# R113X.net
KiCad netlist of a schematic drawn in EAGLE
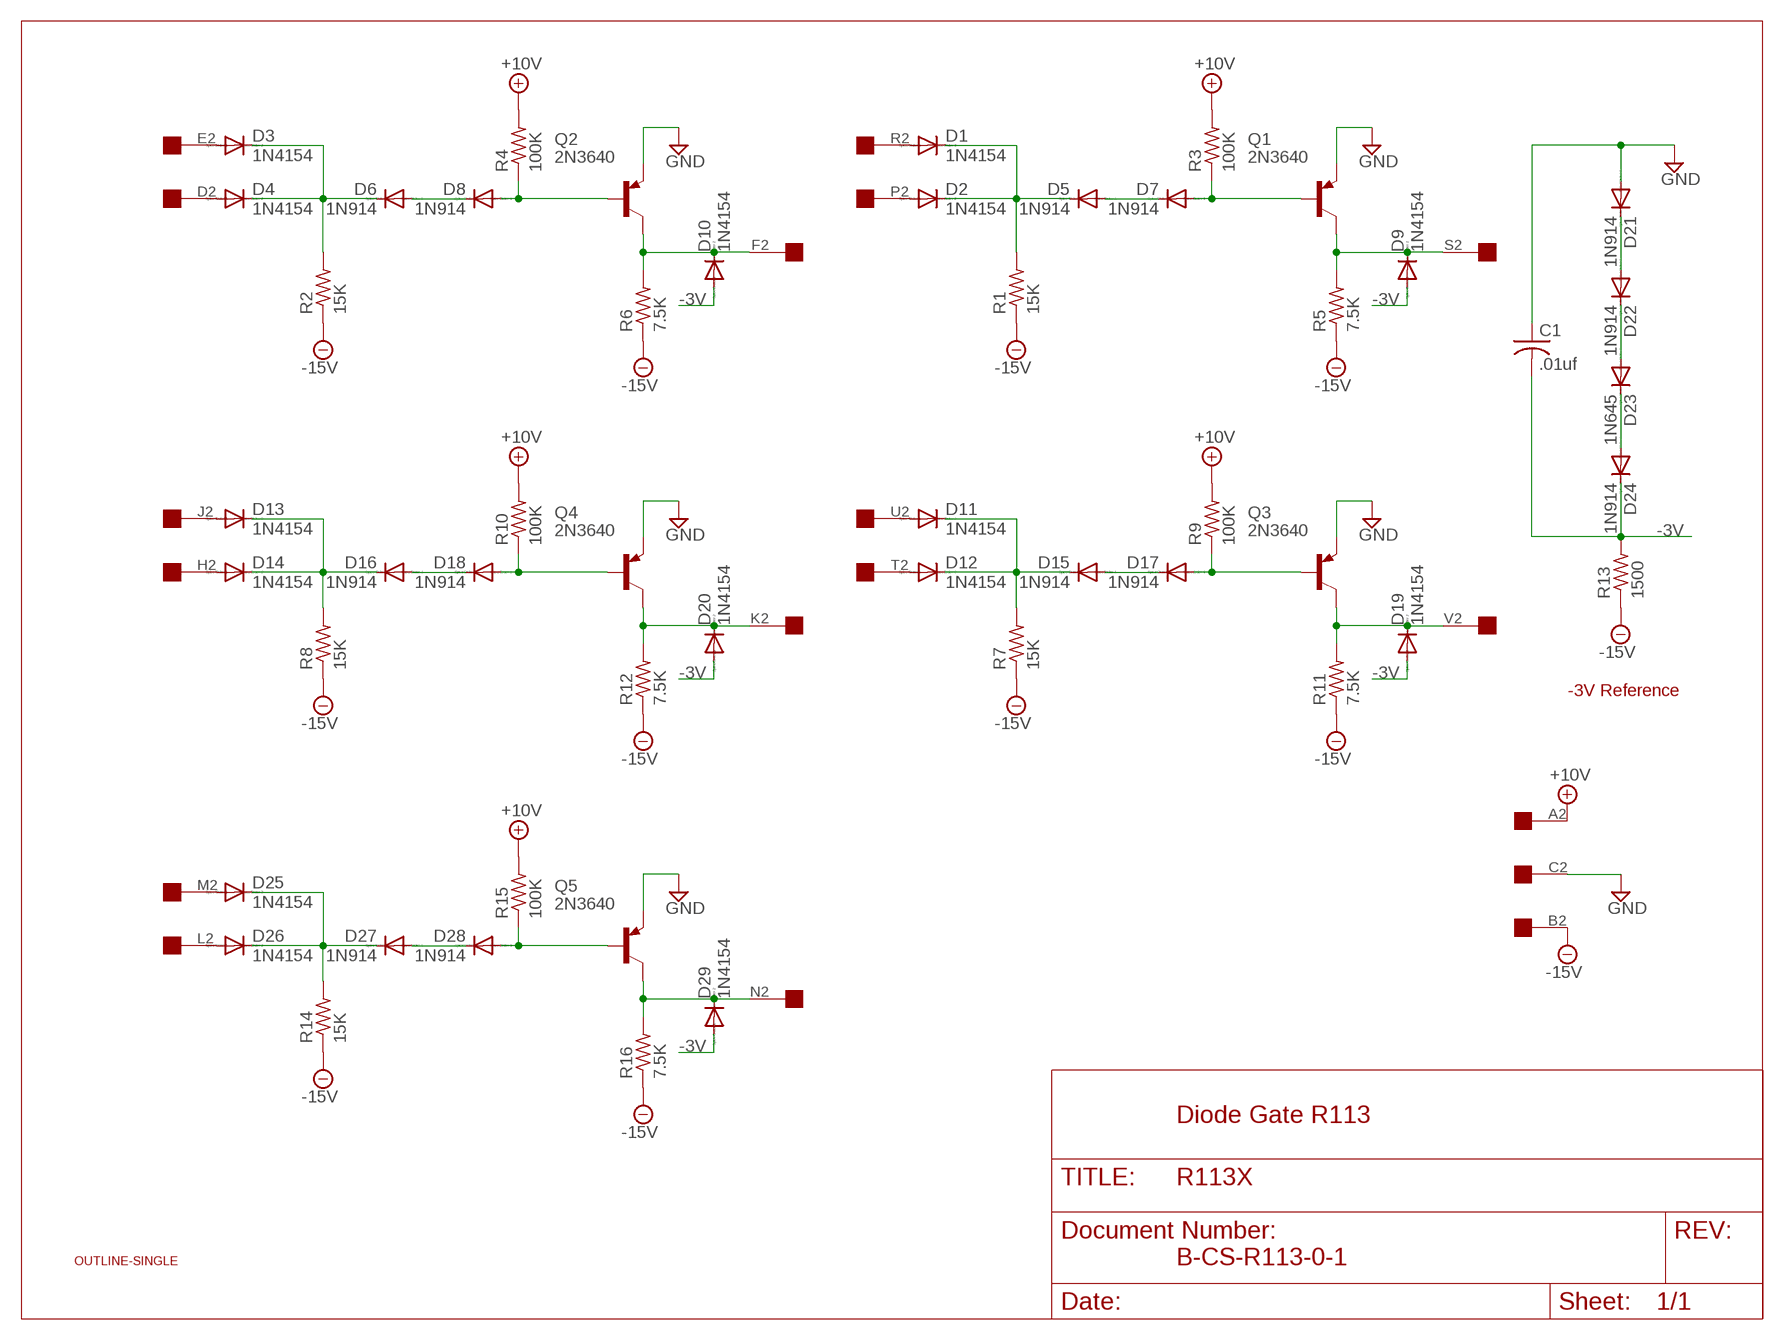
[diagram p0: schematic, sheet 1]

(export (version "E")
  (design (tool "Eeschema 10.0.6"))
  (components
    (comp (ref "C1")
      (value ".01uf")
      (footprint "eagle-import:C050-025X075")
      (libsource (lib "eagle-import") (part "C-US050-025X075"))
    )
    (comp (ref "D1")
      (value "1N4154")
      (footprint "eagle-import:DO35-10")
      (libsource (lib "eagle-import") (part "1N4148DO35-10"))
    )
    (comp (ref "D2")
      (value "1N4154")
      (footprint "eagle-import:DO35-10")
      (libsource (lib "eagle-import") (part "1N4148DO35-10"))
    )
    (comp (ref "D3")
      (value "1N4154")
      (footprint "eagle-import:DO35-10")
      (libsource (lib "eagle-import") (part "1N4148DO35-10"))
    )
    (comp (ref "D4")
      (value "1N4154")
      (footprint "eagle-import:DO35-10")
      (libsource (lib "eagle-import") (part "1N4148DO35-10"))
    )
    (comp (ref "D5")
      (value "1N914")
      (footprint "eagle-import:DO35-10")
      (libsource (lib "eagle-import") (part "1N4148DO35-10"))
    )
    (comp (ref "D6")
      (value "1N914")
      (footprint "eagle-import:DO35-10")
      (libsource (lib "eagle-import") (part "1N4148DO35-10"))
    )
    (comp (ref "D7")
      (value "1N914")
      (footprint "eagle-import:DO35-10")
      (libsource (lib "eagle-import") (part "1N4148DO35-10"))
    )
    (comp (ref "D8")
      (value "1N914")
      (footprint "eagle-import:DO35-10")
      (libsource (lib "eagle-import") (part "1N4148DO35-10"))
    )
    (comp (ref "D9")
      (value "1N4154")
      (footprint "eagle-import:DO35-10")
      (libsource (lib "eagle-import") (part "1N4148DO35-10"))
    )
    (comp (ref "D10")
      (value "1N4154")
      (footprint "eagle-import:DO35-10")
      (libsource (lib "eagle-import") (part "1N4148DO35-10"))
    )
    (comp (ref "D11")
      (value "1N4154")
      (footprint "eagle-import:DO35-10")
      (libsource (lib "eagle-import") (part "1N4148DO35-10"))
    )
    (comp (ref "D12")
      (value "1N4154")
      (footprint "eagle-import:DO35-10")
      (libsource (lib "eagle-import") (part "1N4148DO35-10"))
    )
    (comp (ref "D13")
      (value "1N4154")
      (footprint "eagle-import:DO35-10")
      (libsource (lib "eagle-import") (part "1N4148DO35-10"))
    )
    (comp (ref "D14")
      (value "1N4154")
      (footprint "eagle-import:DO35-10")
      (libsource (lib "eagle-import") (part "1N4148DO35-10"))
    )
    (comp (ref "D15")
      (value "1N914")
      (footprint "eagle-import:DO35-10")
      (libsource (lib "eagle-import") (part "1N4148DO35-10"))
    )
    (comp (ref "D16")
      (value "1N914")
      (footprint "eagle-import:DO35-10")
      (libsource (lib "eagle-import") (part "1N4148DO35-10"))
    )
    (comp (ref "D17")
      (value "1N914")
      (footprint "eagle-import:DO35-10")
      (libsource (lib "eagle-import") (part "1N4148DO35-10"))
    )
    (comp (ref "D18")
      (value "1N914")
      (footprint "eagle-import:DO35-10")
      (libsource (lib "eagle-import") (part "1N4148DO35-10"))
    )
    (comp (ref "D19")
      (value "1N4154")
      (footprint "eagle-import:DO35-10")
      (libsource (lib "eagle-import") (part "1N4148DO35-10"))
    )
    (comp (ref "D20")
      (value "1N4154")
      (footprint "eagle-import:DO35-10")
      (libsource (lib "eagle-import") (part "1N4148DO35-10"))
    )
    (comp (ref "D21")
      (value "1N914")
      (footprint "eagle-import:DO35-10")
      (libsource (lib "eagle-import") (part "1N4148DO35-10"))
    )
    (comp (ref "D22")
      (value "1N914")
      (footprint "eagle-import:DO35-10")
      (libsource (lib "eagle-import") (part "1N4148DO35-10"))
    )
    (comp (ref "D23")
      (value "1N645")
      (footprint "eagle-import:DO35-10")
      (libsource (lib "eagle-import") (part "1N4148DO35-10"))
    )
    (comp (ref "D24")
      (value "1N914")
      (footprint "eagle-import:DO35-10")
      (libsource (lib "eagle-import") (part "1N4148DO35-10"))
    )
    (comp (ref "D25")
      (value "1N4154")
      (footprint "eagle-import:DO35-10")
      (libsource (lib "eagle-import") (part "1N4148DO35-10"))
    )
    (comp (ref "D26")
      (value "1N4154")
      (footprint "eagle-import:DO35-10")
      (libsource (lib "eagle-import") (part "1N4148DO35-10"))
    )
    (comp (ref "D27")
      (value "1N914")
      (footprint "eagle-import:DO35-10")
      (libsource (lib "eagle-import") (part "1N4148DO35-10"))
    )
    (comp (ref "D28")
      (value "1N914")
      (footprint "eagle-import:DO35-10")
      (libsource (lib "eagle-import") (part "1N4148DO35-10"))
    )
    (comp (ref "D29")
      (value "1N4154")
      (footprint "eagle-import:DO35-10")
      (libsource (lib "eagle-import") (part "1N4148DO35-10"))
    )
    (comp (ref "Q1")
      (value "2N3640")
      (footprint "eagle-import:TO39")
      (libsource (lib "eagle-import") (part "2N3637"))
    )
    (comp (ref "Q2")
      (value "2N3640")
      (footprint "eagle-import:TO39")
      (libsource (lib "eagle-import") (part "2N3637"))
    )
    (comp (ref "Q3")
      (value "2N3640")
      (footprint "eagle-import:TO39")
      (libsource (lib "eagle-import") (part "2N3637"))
    )
    (comp (ref "Q4")
      (value "2N3640")
      (footprint "eagle-import:TO39")
      (libsource (lib "eagle-import") (part "2N3637"))
    )
    (comp (ref "Q5")
      (value "2N3640")
      (footprint "eagle-import:TO39")
      (libsource (lib "eagle-import") (part "2N3637"))
    )
    (comp (ref "R1")
      (value "15K")
      (footprint "eagle-import:0207_10")
      (libsource (lib "eagle-import") (part "R-US_0207/10"))
    )
    (comp (ref "R2")
      (value "15K")
      (footprint "eagle-import:0207_10")
      (libsource (lib "eagle-import") (part "R-US_0207/10"))
    )
    (comp (ref "R3")
      (value "100K")
      (footprint "eagle-import:0207_10")
      (libsource (lib "eagle-import") (part "R-US_0207/10"))
    )
    (comp (ref "R4")
      (value "100K")
      (footprint "eagle-import:0207_10")
      (libsource (lib "eagle-import") (part "R-US_0207/10"))
    )
    (comp (ref "R5")
      (value "7.5K")
      (footprint "eagle-import:0207_10")
      (libsource (lib "eagle-import") (part "R-US_0207/10"))
    )
    (comp (ref "R6")
      (value "7.5K")
      (footprint "eagle-import:0207_10")
      (libsource (lib "eagle-import") (part "R-US_0207/10"))
    )
    (comp (ref "R7")
      (value "15K")
      (footprint "eagle-import:0207_10")
      (libsource (lib "eagle-import") (part "R-US_0207/10"))
    )
    (comp (ref "R8")
      (value "15K")
      (footprint "eagle-import:0207_10")
      (libsource (lib "eagle-import") (part "R-US_0207/10"))
    )
    (comp (ref "R9")
      (value "100K")
      (footprint "eagle-import:0207_10")
      (libsource (lib "eagle-import") (part "R-US_0207/10"))
    )
    (comp (ref "R10")
      (value "100K")
      (footprint "eagle-import:0207_10")
      (libsource (lib "eagle-import") (part "R-US_0207/10"))
    )
    (comp (ref "R11")
      (value "7.5K")
      (footprint "eagle-import:0207_10")
      (libsource (lib "eagle-import") (part "R-US_0207/10"))
    )
    (comp (ref "R12")
      (value "7.5K")
      (footprint "eagle-import:0207_10")
      (libsource (lib "eagle-import") (part "R-US_0207/10"))
    )
    (comp (ref "R13")
      (value "1500")
      (footprint "eagle-import:0207_10")
      (libsource (lib "eagle-import") (part "R-US_0207/10"))
    )
    (comp (ref "R14")
      (value "15K")
      (footprint "eagle-import:0207_10")
      (libsource (lib "eagle-import") (part "R-US_0207/10"))
    )
    (comp (ref "R15")
      (value "100K")
      (footprint "eagle-import:0207_10")
      (libsource (lib "eagle-import") (part "R-US_0207/10"))
    )
    (comp (ref "R16")
      (value "7.5K")
      (footprint "eagle-import:0207_10")
      (libsource (lib "eagle-import") (part "R-US_0207/10"))
    )
    (comp (ref "U$1")
      (value "OUTLINE-SINGLE")
      (footprint "eagle-import:SINGLE")
      (libsource (lib "eagle-import") (part "OUTLINE-SINGLE"))
    )
    (comp (ref "U$2")
      (value "EDGE-1")
      (footprint "eagle-import:EDGE-CON1")
      (libsource (lib "eagle-import") (part "EDGE-1"))
    )
  )
  (nets
    (net (code "1") (name "+10V") (class "Default")
      (node (ref "R10") (pin "2") (pinfunction "2_2") (pintype "passive"))
      (node (ref "R15") (pin "2") (pinfunction "2_2") (pintype "passive"))
      (node (ref "R3") (pin "2") (pinfunction "2_2") (pintype "passive"))
      (node (ref "R4") (pin "2") (pinfunction "2_2") (pintype "passive"))
      (node (ref "R9") (pin "2") (pinfunction "2_2") (pintype "passive"))
      (node (ref "U$2") (pin "A2") (pinfunction "1_A2") (pintype "bidirectional"))
    )
    (net (code "2") (name "-15V") (class "Default")
      (node (ref "R1") (pin "1") (pinfunction "1_1") (pintype "passive"))
      (node (ref "R11") (pin "1") (pinfunction "1_1") (pintype "passive"))
      (node (ref "R12") (pin "1") (pinfunction "1_1") (pintype "passive"))
      (node (ref "R13") (pin "1") (pinfunction "1_1") (pintype "passive"))
      (node (ref "R14") (pin "1") (pinfunction "1_1") (pintype "passive"))
      (node (ref "R16") (pin "1") (pinfunction "1_1") (pintype "passive"))
      (node (ref "R2") (pin "1") (pinfunction "1_1") (pintype "passive"))
      (node (ref "R5") (pin "1") (pinfunction "1_1") (pintype "passive"))
      (node (ref "R6") (pin "1") (pinfunction "1_1") (pintype "passive"))
      (node (ref "R7") (pin "1") (pinfunction "1_1") (pintype "passive"))
      (node (ref "R8") (pin "1") (pinfunction "1_1") (pintype "passive"))
      (node (ref "U$2") (pin "B2") (pinfunction "1_B2") (pintype "bidirectional"))
    )
    (net (code "3") (name "/-3V") (class "Default")
      (node (ref "C1") (pin "2") (pinfunction "2_2") (pintype "passive"))
      (node (ref "D10") (pin "A") (pinfunction "A_A") (pintype "passive"))
      (node (ref "D19") (pin "A") (pinfunction "A_A") (pintype "passive"))
      (node (ref "D20") (pin "A") (pinfunction "A_A") (pintype "passive"))
      (node (ref "D24") (pin "C") (pinfunction "C_C") (pintype "passive"))
      (node (ref "D29") (pin "A") (pinfunction "A_A") (pintype "passive"))
      (node (ref "D9") (pin "A") (pinfunction "A_A") (pintype "passive"))
      (node (ref "R13") (pin "2") (pinfunction "2_2") (pintype "passive"))
    )
    (net (code "4") (name "GND") (class "Default")
      (node (ref "C1") (pin "1") (pinfunction "1_1") (pintype "passive"))
      (node (ref "D21") (pin "A") (pinfunction "A_A") (pintype "passive"))
      (node (ref "Q1") (pin "1") (pinfunction "E_1") (pintype "passive"))
      (node (ref "Q2") (pin "1") (pinfunction "E_1") (pintype "passive"))
      (node (ref "Q3") (pin "1") (pinfunction "E_1") (pintype "passive"))
      (node (ref "Q4") (pin "1") (pinfunction "E_1") (pintype "passive"))
      (node (ref "Q5") (pin "1") (pinfunction "E_1") (pintype "passive"))
      (node (ref "U$2") (pin "C2") (pinfunction "1_C2") (pintype "bidirectional"))
    )
    (net (code "5") (name "Net-(D1-PadC)") (class "Default")
      (node (ref "D1") (pin "C") (pinfunction "C_C") (pintype "passive"))
      (node (ref "D2") (pin "C") (pinfunction "C_C") (pintype "passive"))
      (node (ref "D5") (pin "C") (pinfunction "C_C") (pintype "passive"))
      (node (ref "R1") (pin "2") (pinfunction "2_2") (pintype "passive"))
    )
    (net (code "6") (name "Net-(D3-PadC)") (class "Default")
      (node (ref "D3") (pin "C") (pinfunction "C_C") (pintype "passive"))
      (node (ref "D4") (pin "C") (pinfunction "C_C") (pintype "passive"))
      (node (ref "D6") (pin "C") (pinfunction "C_C") (pintype "passive"))
      (node (ref "R2") (pin "2") (pinfunction "2_2") (pintype "passive"))
    )
    (net (code "7") (name "Net-(D5-PadA)") (class "Default")
      (node (ref "D5") (pin "A") (pinfunction "A_A") (pintype "passive"))
      (node (ref "D7") (pin "C") (pinfunction "C_C") (pintype "passive"))
    )
    (net (code "8") (name "Net-(D6-PadA)") (class "Default")
      (node (ref "D6") (pin "A") (pinfunction "A_A") (pintype "passive"))
      (node (ref "D8") (pin "C") (pinfunction "C_C") (pintype "passive"))
    )
    (net (code "9") (name "Net-(D11-PadC)") (class "Default")
      (node (ref "D11") (pin "C") (pinfunction "C_C") (pintype "passive"))
      (node (ref "D12") (pin "C") (pinfunction "C_C") (pintype "passive"))
      (node (ref "D15") (pin "C") (pinfunction "C_C") (pintype "passive"))
      (node (ref "R7") (pin "2") (pinfunction "2_2") (pintype "passive"))
    )
    (net (code "10") (name "Net-(D13-PadC)") (class "Default")
      (node (ref "D13") (pin "C") (pinfunction "C_C") (pintype "passive"))
      (node (ref "D14") (pin "C") (pinfunction "C_C") (pintype "passive"))
      (node (ref "D16") (pin "C") (pinfunction "C_C") (pintype "passive"))
      (node (ref "R8") (pin "2") (pinfunction "2_2") (pintype "passive"))
    )
    (net (code "11") (name "Net-(D15-PadA)") (class "Default")
      (node (ref "D15") (pin "A") (pinfunction "A_A") (pintype "passive"))
      (node (ref "D17") (pin "C") (pinfunction "C_C") (pintype "passive"))
    )
    (net (code "12") (name "Net-(D16-PadA)") (class "Default")
      (node (ref "D16") (pin "A") (pinfunction "A_A") (pintype "passive"))
      (node (ref "D18") (pin "C") (pinfunction "C_C") (pintype "passive"))
    )
    (net (code "13") (name "Net-(D21-PadC)") (class "Default")
      (node (ref "D21") (pin "C") (pinfunction "C_C") (pintype "passive"))
      (node (ref "D22") (pin "A") (pinfunction "A_A") (pintype "passive"))
    )
    (net (code "14") (name "Net-(D22-PadC)") (class "Default")
      (node (ref "D22") (pin "C") (pinfunction "C_C") (pintype "passive"))
      (node (ref "D23") (pin "A") (pinfunction "A_A") (pintype "passive"))
    )
    (net (code "15") (name "Net-(D23-PadC)") (class "Default")
      (node (ref "D23") (pin "C") (pinfunction "C_C") (pintype "passive"))
      (node (ref "D24") (pin "A") (pinfunction "A_A") (pintype "passive"))
    )
    (net (code "16") (name "Net-(D25-PadC)") (class "Default")
      (node (ref "D25") (pin "C") (pinfunction "C_C") (pintype "passive"))
      (node (ref "D26") (pin "C") (pinfunction "C_C") (pintype "passive"))
      (node (ref "D27") (pin "C") (pinfunction "C_C") (pintype "passive"))
      (node (ref "R14") (pin "2") (pinfunction "2_2") (pintype "passive"))
    )
    (net (code "17") (name "Net-(D27-PadA)") (class "Default")
      (node (ref "D27") (pin "A") (pinfunction "A_A") (pintype "passive"))
      (node (ref "D28") (pin "C") (pinfunction "C_C") (pintype "passive"))
    )
    (net (code "18") (name "Net-(Q1-B)") (class "Default")
      (node (ref "D7") (pin "A") (pinfunction "A_A") (pintype "passive"))
      (node (ref "Q1") (pin "2") (pinfunction "B_2") (pintype "passive"))
      (node (ref "R3") (pin "1") (pinfunction "1_1") (pintype "passive"))
    )
    (net (code "19") (name "Net-(Q1-C)") (class "Default")
      (node (ref "D9") (pin "C") (pinfunction "C_C") (pintype "passive"))
      (node (ref "Q1") (pin "3") (pinfunction "C_3") (pintype "passive"))
      (node (ref "R5") (pin "2") (pinfunction "2_2") (pintype "passive"))
      (node (ref "U$2") (pin "S2") (pinfunction "1_S2") (pintype "bidirectional"))
    )
    (net (code "20") (name "Net-(Q2-B)") (class "Default")
      (node (ref "D8") (pin "A") (pinfunction "A_A") (pintype "passive"))
      (node (ref "Q2") (pin "2") (pinfunction "B_2") (pintype "passive"))
      (node (ref "R4") (pin "1") (pinfunction "1_1") (pintype "passive"))
    )
    (net (code "21") (name "Net-(Q2-C)") (class "Default")
      (node (ref "D10") (pin "C") (pinfunction "C_C") (pintype "passive"))
      (node (ref "Q2") (pin "3") (pinfunction "C_3") (pintype "passive"))
      (node (ref "R6") (pin "2") (pinfunction "2_2") (pintype "passive"))
      (node (ref "U$2") (pin "F2") (pinfunction "1_F2") (pintype "bidirectional"))
    )
    (net (code "22") (name "Net-(Q3-B)") (class "Default")
      (node (ref "D17") (pin "A") (pinfunction "A_A") (pintype "passive"))
      (node (ref "Q3") (pin "2") (pinfunction "B_2") (pintype "passive"))
      (node (ref "R9") (pin "1") (pinfunction "1_1") (pintype "passive"))
    )
    (net (code "23") (name "Net-(Q3-C)") (class "Default")
      (node (ref "D19") (pin "C") (pinfunction "C_C") (pintype "passive"))
      (node (ref "Q3") (pin "3") (pinfunction "C_3") (pintype "passive"))
      (node (ref "R11") (pin "2") (pinfunction "2_2") (pintype "passive"))
      (node (ref "U$2") (pin "V2") (pinfunction "1_V2") (pintype "bidirectional"))
    )
    (net (code "24") (name "Net-(Q4-B)") (class "Default")
      (node (ref "D18") (pin "A") (pinfunction "A_A") (pintype "passive"))
      (node (ref "Q4") (pin "2") (pinfunction "B_2") (pintype "passive"))
      (node (ref "R10") (pin "1") (pinfunction "1_1") (pintype "passive"))
    )
    (net (code "25") (name "Net-(Q4-C)") (class "Default")
      (node (ref "D20") (pin "C") (pinfunction "C_C") (pintype "passive"))
      (node (ref "Q4") (pin "3") (pinfunction "C_3") (pintype "passive"))
      (node (ref "R12") (pin "2") (pinfunction "2_2") (pintype "passive"))
      (node (ref "U$2") (pin "K2") (pinfunction "1_K2") (pintype "bidirectional"))
    )
    (net (code "26") (name "Net-(Q5-B)") (class "Default")
      (node (ref "D28") (pin "A") (pinfunction "A_A") (pintype "passive"))
      (node (ref "Q5") (pin "2") (pinfunction "B_2") (pintype "passive"))
      (node (ref "R15") (pin "1") (pinfunction "1_1") (pintype "passive"))
    )
    (net (code "27") (name "Net-(Q5-C)") (class "Default")
      (node (ref "D29") (pin "C") (pinfunction "C_C") (pintype "passive"))
      (node (ref "Q5") (pin "3") (pinfunction "C_3") (pintype "passive"))
      (node (ref "R16") (pin "2") (pinfunction "2_2") (pintype "passive"))
      (node (ref "U$2") (pin "N2") (pinfunction "1_N2") (pintype "bidirectional"))
    )
    (net (code "28") (name "Net-(U$2D-1)") (class "Default")
      (node (ref "D4") (pin "A") (pinfunction "A_A") (pintype "passive"))
      (node (ref "U$2") (pin "D2") (pinfunction "1_D2") (pintype "bidirectional"))
    )
    (net (code "29") (name "Net-(U$2E-1)") (class "Default")
      (node (ref "D3") (pin "A") (pinfunction "A_A") (pintype "passive"))
      (node (ref "U$2") (pin "E2") (pinfunction "1_E2") (pintype "bidirectional"))
    )
    (net (code "30") (name "Net-(U$2G-1)") (class "Default")
      (node (ref "D14") (pin "A") (pinfunction "A_A") (pintype "passive"))
      (node (ref "U$2") (pin "H2") (pinfunction "1_H2") (pintype "bidirectional"))
    )
    (net (code "31") (name "Net-(U$2H-1)") (class "Default")
      (node (ref "D13") (pin "A") (pinfunction "A_A") (pintype "passive"))
      (node (ref "U$2") (pin "J2") (pinfunction "1_J2") (pintype "bidirectional"))
    )
    (net (code "32") (name "Net-(U$2J-1)") (class "Default")
      (node (ref "D26") (pin "A") (pinfunction "A_A") (pintype "passive"))
      (node (ref "U$2") (pin "L2") (pinfunction "1_L2") (pintype "bidirectional"))
    )
    (net (code "33") (name "Net-(U$2K-1)") (class "Default")
      (node (ref "D25") (pin "A") (pinfunction "A_A") (pintype "passive"))
      (node (ref "U$2") (pin "M2") (pinfunction "1_M2") (pintype "bidirectional"))
    )
    (net (code "34") (name "Net-(U$2M-1)") (class "Default")
      (node (ref "D2") (pin "A") (pinfunction "A_A") (pintype "passive"))
      (node (ref "U$2") (pin "P2") (pinfunction "1_P2") (pintype "bidirectional"))
    )
    (net (code "35") (name "Net-(U$2N-1)") (class "Default")
      (node (ref "D1") (pin "A") (pinfunction "A_A") (pintype "passive"))
      (node (ref "U$2") (pin "R2") (pinfunction "1_R2") (pintype "bidirectional"))
    )
    (net (code "36") (name "Net-(U$2P-1)") (class "Default")
      (node (ref "D12") (pin "A") (pinfunction "A_A") (pintype "passive"))
      (node (ref "U$2") (pin "T2") (pinfunction "1_T2") (pintype "bidirectional"))
    )
    (net (code "37") (name "Net-(U$2Q-1)") (class "Default")
      (node (ref "D11") (pin "A") (pinfunction "A_A") (pintype "passive"))
      (node (ref "U$2") (pin "U2") (pinfunction "1_U2") (pintype "bidirectional"))
    )
  )
)
